# turntable_ir_5.net
KiCad netlist of a schematic drawn in EAGLE
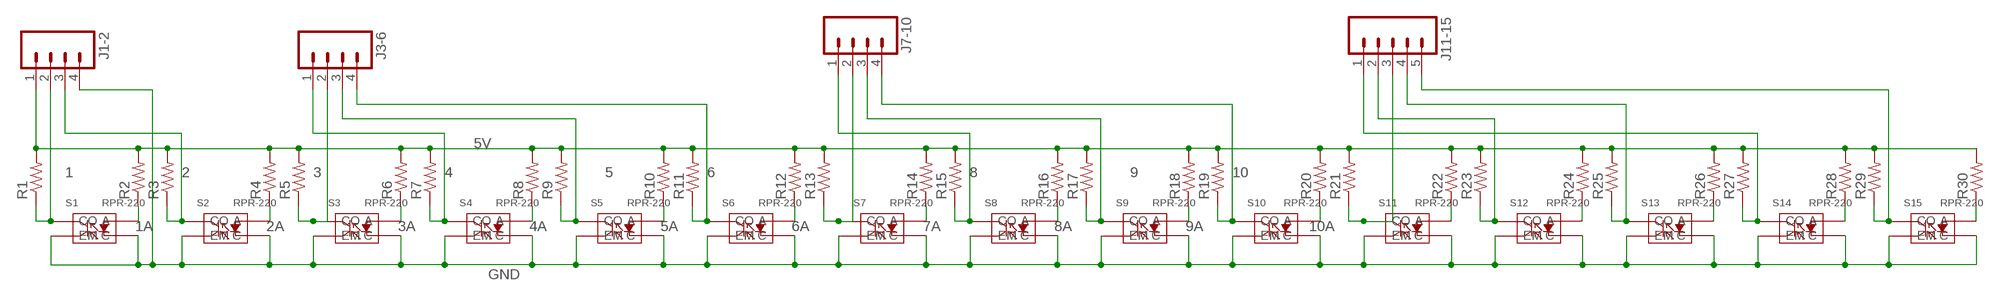
[diagram p0: schematic, sheet 1]

(export (version "E")
  (design (tool "Eeschema 10.0.6"))
  (components
    (comp (ref "J1-2")
      (value "M04NO_SILK_ALL_ROUND")
      (footprint "eagle-import:1X04_NO_SILK_ALL_ROUND")
      (libsource (lib "eagle-import") (part "M04NO_SILK_ALL_ROUND"))
    )
    (comp (ref "J3-6")
      (value "M04NO_SILK_ALL_ROUND")
      (footprint "eagle-import:1X04_NO_SILK_ALL_ROUND")
      (libsource (lib "eagle-import") (part "M04NO_SILK_ALL_ROUND"))
    )
    (comp (ref "J7-10")
      (value "M04NO_SILK_ALL_ROUND")
      (footprint "eagle-import:1X04_NO_SILK_ALL_ROUND")
      (libsource (lib "eagle-import") (part "M04NO_SILK_ALL_ROUND"))
    )
    (comp (ref "J11-15")
      (value "M05NO_SILK")
      (footprint "eagle-import:1X05_NO_SILK")
      (libsource (lib "eagle-import") (part "M05NO_SILK"))
    )
    (comp (ref "R1")
      (value "RESISTOR1206")
      (footprint "eagle-import:1206")
      (libsource (lib "eagle-import") (part "RESISTOR1206"))
    )
    (comp (ref "R2")
      (value "RESISTOR1206")
      (footprint "eagle-import:1206")
      (libsource (lib "eagle-import") (part "RESISTOR1206"))
    )
    (comp (ref "R3")
      (value "RESISTOR1206")
      (footprint "eagle-import:1206")
      (libsource (lib "eagle-import") (part "RESISTOR1206"))
    )
    (comp (ref "R4")
      (value "RESISTOR1206")
      (footprint "eagle-import:1206")
      (libsource (lib "eagle-import") (part "RESISTOR1206"))
    )
    (comp (ref "R5")
      (value "RESISTOR1206")
      (footprint "eagle-import:1206")
      (libsource (lib "eagle-import") (part "RESISTOR1206"))
    )
    (comp (ref "R6")
      (value "RESISTOR1206")
      (footprint "eagle-import:1206")
      (libsource (lib "eagle-import") (part "RESISTOR1206"))
    )
    (comp (ref "R7")
      (value "RESISTOR1206")
      (footprint "eagle-import:1206")
      (libsource (lib "eagle-import") (part "RESISTOR1206"))
    )
    (comp (ref "R8")
      (value "RESISTOR1206")
      (footprint "eagle-import:1206")
      (libsource (lib "eagle-import") (part "RESISTOR1206"))
    )
    (comp (ref "R9")
      (value "RESISTOR1206")
      (footprint "eagle-import:1206")
      (libsource (lib "eagle-import") (part "RESISTOR1206"))
    )
    (comp (ref "R10")
      (value "RESISTOR1206")
      (footprint "eagle-import:1206")
      (libsource (lib "eagle-import") (part "RESISTOR1206"))
    )
    (comp (ref "R11")
      (value "RESISTOR1206")
      (footprint "eagle-import:1206")
      (libsource (lib "eagle-import") (part "RESISTOR1206"))
    )
    (comp (ref "R12")
      (value "RESISTOR1206")
      (footprint "eagle-import:1206")
      (libsource (lib "eagle-import") (part "RESISTOR1206"))
    )
    (comp (ref "R13")
      (value "RESISTOR1206")
      (footprint "eagle-import:1206")
      (libsource (lib "eagle-import") (part "RESISTOR1206"))
    )
    (comp (ref "R14")
      (value "RESISTOR1206")
      (footprint "eagle-import:1206")
      (libsource (lib "eagle-import") (part "RESISTOR1206"))
    )
    (comp (ref "R15")
      (value "RESISTOR1206")
      (footprint "eagle-import:1206")
      (libsource (lib "eagle-import") (part "RESISTOR1206"))
    )
    (comp (ref "R16")
      (value "RESISTOR1206")
      (footprint "eagle-import:1206")
      (libsource (lib "eagle-import") (part "RESISTOR1206"))
    )
    (comp (ref "R17")
      (value "RESISTOR1206")
      (footprint "eagle-import:1206")
      (libsource (lib "eagle-import") (part "RESISTOR1206"))
    )
    (comp (ref "R18")
      (value "RESISTOR1206")
      (footprint "eagle-import:1206")
      (libsource (lib "eagle-import") (part "RESISTOR1206"))
    )
    (comp (ref "R19")
      (value "RESISTOR1206")
      (footprint "eagle-import:1206")
      (libsource (lib "eagle-import") (part "RESISTOR1206"))
    )
    (comp (ref "R20")
      (value "RESISTOR1206")
      (footprint "eagle-import:1206")
      (libsource (lib "eagle-import") (part "RESISTOR1206"))
    )
    (comp (ref "R21")
      (value "RESISTOR1206")
      (footprint "eagle-import:1206")
      (libsource (lib "eagle-import") (part "RESISTOR1206"))
    )
    (comp (ref "R22")
      (value "RESISTOR1206")
      (footprint "eagle-import:1206")
      (libsource (lib "eagle-import") (part "RESISTOR1206"))
    )
    (comp (ref "R23")
      (value "RESISTOR1206")
      (footprint "eagle-import:1206")
      (libsource (lib "eagle-import") (part "RESISTOR1206"))
    )
    (comp (ref "R24")
      (value "RESISTOR1206")
      (footprint "eagle-import:1206")
      (libsource (lib "eagle-import") (part "RESISTOR1206"))
    )
    (comp (ref "R25")
      (value "RESISTOR1206")
      (footprint "eagle-import:1206")
      (libsource (lib "eagle-import") (part "RESISTOR1206"))
    )
    (comp (ref "R26")
      (value "RESISTOR1206")
      (footprint "eagle-import:1206")
      (libsource (lib "eagle-import") (part "RESISTOR1206"))
    )
    (comp (ref "R27")
      (value "RESISTOR1206")
      (footprint "eagle-import:1206")
      (libsource (lib "eagle-import") (part "RESISTOR1206"))
    )
    (comp (ref "R28")
      (value "RESISTOR1206")
      (footprint "eagle-import:1206")
      (libsource (lib "eagle-import") (part "RESISTOR1206"))
    )
    (comp (ref "R29")
      (value "RESISTOR1206")
      (footprint "eagle-import:1206")
      (libsource (lib "eagle-import") (part "RESISTOR1206"))
    )
    (comp (ref "R30")
      (value "RESISTOR1206")
      (footprint "eagle-import:1206")
      (libsource (lib "eagle-import") (part "RESISTOR1206"))
    )
    (comp (ref "S1")
      (value "RPR-220")
      (footprint "eagle-import:RPR-220-6.4X4.9X6.5")
      (libsource (lib "eagle-import") (part "RPR-220"))
    )
    (comp (ref "S2")
      (value "RPR-220")
      (footprint "eagle-import:RPR-220-6.4X4.9X6.5")
      (libsource (lib "eagle-import") (part "RPR-220"))
    )
    (comp (ref "S3")
      (value "RPR-220")
      (footprint "eagle-import:RPR-220-6.4X4.9X6.5")
      (libsource (lib "eagle-import") (part "RPR-220"))
    )
    (comp (ref "S4")
      (value "RPR-220")
      (footprint "eagle-import:RPR-220-6.4X4.9X6.5")
      (libsource (lib "eagle-import") (part "RPR-220"))
    )
    (comp (ref "S5")
      (value "RPR-220")
      (footprint "eagle-import:RPR-220-6.4X4.9X6.5")
      (libsource (lib "eagle-import") (part "RPR-220"))
    )
    (comp (ref "S6")
      (value "RPR-220")
      (footprint "eagle-import:RPR-220-6.4X4.9X6.5")
      (libsource (lib "eagle-import") (part "RPR-220"))
    )
    (comp (ref "S7")
      (value "RPR-220")
      (footprint "eagle-import:RPR-220-6.4X4.9X6.5")
      (libsource (lib "eagle-import") (part "RPR-220"))
    )
    (comp (ref "S8")
      (value "RPR-220")
      (footprint "eagle-import:RPR-220-6.4X4.9X6.5")
      (libsource (lib "eagle-import") (part "RPR-220"))
    )
    (comp (ref "S9")
      (value "RPR-220")
      (footprint "eagle-import:RPR-220-6.4X4.9X6.5")
      (libsource (lib "eagle-import") (part "RPR-220"))
    )
    (comp (ref "S10")
      (value "RPR-220")
      (footprint "eagle-import:RPR-220-6.4X4.9X6.5")
      (libsource (lib "eagle-import") (part "RPR-220"))
    )
    (comp (ref "S11")
      (value "RPR-220")
      (footprint "eagle-import:RPR-220-6.4X4.9X6.5")
      (libsource (lib "eagle-import") (part "RPR-220"))
    )
    (comp (ref "S12")
      (value "RPR-220")
      (footprint "eagle-import:RPR-220-6.4X4.9X6.5")
      (libsource (lib "eagle-import") (part "RPR-220"))
    )
    (comp (ref "S13")
      (value "RPR-220")
      (footprint "eagle-import:RPR-220-6.4X4.9X6.5")
      (libsource (lib "eagle-import") (part "RPR-220"))
    )
    (comp (ref "S14")
      (value "RPR-220")
      (footprint "eagle-import:RPR-220-6.4X4.9X6.5")
      (libsource (lib "eagle-import") (part "RPR-220"))
    )
    (comp (ref "S15")
      (value "RPR-220")
      (footprint "eagle-import:RPR-220-6.4X4.9X6.5")
      (libsource (lib "eagle-import") (part "RPR-220"))
    )
  )
  (nets
    (net (code "1") (name "/1") (class "Default")
      (node (ref "J1-2") (pin "2") (pinfunction "2_2") (pintype "passive"))
      (node (ref "R1") (pin "1") (pinfunction "1_1") (pintype "passive"))
      (node (ref "S1") (pin "P$4") (pinfunction "CO_P$4") (pintype "bidirectional"))
    )
    (net (code "2") (name "/1A") (class "Default")
      (node (ref "R2") (pin "1") (pinfunction "1_1") (pintype "passive"))
      (node (ref "S1") (pin "P$1") (pinfunction "A_P$1") (pintype "bidirectional"))
    )
    (net (code "3") (name "/2") (class "Default")
      (node (ref "J1-2") (pin "3") (pinfunction "3_3") (pintype "passive"))
      (node (ref "R3") (pin "1") (pinfunction "1_1") (pintype "passive"))
      (node (ref "S2") (pin "P$4") (pinfunction "CO_P$4") (pintype "bidirectional"))
    )
    (net (code "4") (name "/2A") (class "Default")
      (node (ref "R4") (pin "1") (pinfunction "1_1") (pintype "passive"))
      (node (ref "S2") (pin "P$1") (pinfunction "A_P$1") (pintype "bidirectional"))
    )
    (net (code "5") (name "/3") (class "Default")
      (node (ref "J3-6") (pin "2") (pinfunction "2_2") (pintype "passive"))
      (node (ref "R5") (pin "1") (pinfunction "1_1") (pintype "passive"))
      (node (ref "S3") (pin "P$4") (pinfunction "CO_P$4") (pintype "bidirectional"))
    )
    (net (code "6") (name "/3A") (class "Default")
      (node (ref "R6") (pin "1") (pinfunction "1_1") (pintype "passive"))
      (node (ref "S3") (pin "P$1") (pinfunction "A_P$1") (pintype "bidirectional"))
    )
    (net (code "7") (name "/4") (class "Default")
      (node (ref "J3-6") (pin "1") (pinfunction "1_1") (pintype "passive"))
      (node (ref "R7") (pin "1") (pinfunction "1_1") (pintype "passive"))
      (node (ref "S4") (pin "P$4") (pinfunction "CO_P$4") (pintype "bidirectional"))
    )
    (net (code "8") (name "/4A") (class "Default")
      (node (ref "R8") (pin "1") (pinfunction "1_1") (pintype "passive"))
      (node (ref "S4") (pin "P$1") (pinfunction "A_P$1") (pintype "bidirectional"))
    )
    (net (code "9") (name "/5") (class "Default")
      (node (ref "J3-6") (pin "3") (pinfunction "3_3") (pintype "passive"))
      (node (ref "R9") (pin "1") (pinfunction "1_1") (pintype "passive"))
      (node (ref "S5") (pin "P$4") (pinfunction "CO_P$4") (pintype "bidirectional"))
    )
    (net (code "10") (name "/5A") (class "Default")
      (node (ref "R10") (pin "1") (pinfunction "1_1") (pintype "passive"))
      (node (ref "S5") (pin "P$1") (pinfunction "A_P$1") (pintype "bidirectional"))
    )
    (net (code "11") (name "/5V") (class "Default")
      (node (ref "J1-2") (pin "1") (pinfunction "1_1") (pintype "passive"))
      (node (ref "R1") (pin "2") (pinfunction "2_2") (pintype "passive"))
      (node (ref "R10") (pin "2") (pinfunction "2_2") (pintype "passive"))
      (node (ref "R11") (pin "2") (pinfunction "2_2") (pintype "passive"))
      (node (ref "R12") (pin "2") (pinfunction "2_2") (pintype "passive"))
      (node (ref "R13") (pin "2") (pinfunction "2_2") (pintype "passive"))
      (node (ref "R14") (pin "2") (pinfunction "2_2") (pintype "passive"))
      (node (ref "R15") (pin "2") (pinfunction "2_2") (pintype "passive"))
      (node (ref "R16") (pin "2") (pinfunction "2_2") (pintype "passive"))
      (node (ref "R17") (pin "2") (pinfunction "2_2") (pintype "passive"))
      (node (ref "R18") (pin "2") (pinfunction "2_2") (pintype "passive"))
      (node (ref "R19") (pin "2") (pinfunction "2_2") (pintype "passive"))
      (node (ref "R2") (pin "2") (pinfunction "2_2") (pintype "passive"))
      (node (ref "R20") (pin "2") (pinfunction "2_2") (pintype "passive"))
      (node (ref "R21") (pin "2") (pinfunction "2_2") (pintype "passive"))
      (node (ref "R22") (pin "2") (pinfunction "2_2") (pintype "passive"))
      (node (ref "R23") (pin "2") (pinfunction "2_2") (pintype "passive"))
      (node (ref "R24") (pin "2") (pinfunction "2_2") (pintype "passive"))
      (node (ref "R25") (pin "2") (pinfunction "2_2") (pintype "passive"))
      (node (ref "R26") (pin "2") (pinfunction "2_2") (pintype "passive"))
      (node (ref "R27") (pin "2") (pinfunction "2_2") (pintype "passive"))
      (node (ref "R28") (pin "2") (pinfunction "2_2") (pintype "passive"))
      (node (ref "R29") (pin "2") (pinfunction "2_2") (pintype "passive"))
      (node (ref "R3") (pin "2") (pinfunction "2_2") (pintype "passive"))
      (node (ref "R30") (pin "2") (pinfunction "2_2") (pintype "passive"))
      (node (ref "R4") (pin "2") (pinfunction "2_2") (pintype "passive"))
      (node (ref "R5") (pin "2") (pinfunction "2_2") (pintype "passive"))
      (node (ref "R6") (pin "2") (pinfunction "2_2") (pintype "passive"))
      (node (ref "R7") (pin "2") (pinfunction "2_2") (pintype "passive"))
      (node (ref "R8") (pin "2") (pinfunction "2_2") (pintype "passive"))
      (node (ref "R9") (pin "2") (pinfunction "2_2") (pintype "passive"))
    )
    (net (code "12") (name "/6") (class "Default")
      (node (ref "J3-6") (pin "4") (pinfunction "4_4") (pintype "passive"))
      (node (ref "R11") (pin "1") (pinfunction "1_1") (pintype "passive"))
      (node (ref "S6") (pin "P$4") (pinfunction "CO_P$4") (pintype "bidirectional"))
    )
    (net (code "13") (name "/6A") (class "Default")
      (node (ref "R12") (pin "1") (pinfunction "1_1") (pintype "passive"))
      (node (ref "S6") (pin "P$1") (pinfunction "A_P$1") (pintype "bidirectional"))
    )
    (net (code "14") (name "/7A") (class "Default")
      (node (ref "R14") (pin "1") (pinfunction "1_1") (pintype "passive"))
      (node (ref "S7") (pin "P$1") (pinfunction "A_P$1") (pintype "bidirectional"))
    )
    (net (code "15") (name "/8") (class "Default")
      (node (ref "J7-10") (pin "1") (pinfunction "1_1") (pintype "passive"))
      (node (ref "R15") (pin "1") (pinfunction "1_1") (pintype "passive"))
      (node (ref "S8") (pin "P$4") (pinfunction "CO_P$4") (pintype "bidirectional"))
    )
    (net (code "16") (name "/8A") (class "Default")
      (node (ref "R16") (pin "1") (pinfunction "1_1") (pintype "passive"))
      (node (ref "S8") (pin "P$1") (pinfunction "A_P$1") (pintype "bidirectional"))
    )
    (net (code "17") (name "/9") (class "Default")
      (node (ref "J7-10") (pin "3") (pinfunction "3_3") (pintype "passive"))
      (node (ref "R17") (pin "1") (pinfunction "1_1") (pintype "passive"))
      (node (ref "S9") (pin "P$4") (pinfunction "CO_P$4") (pintype "bidirectional"))
    )
    (net (code "18") (name "/9A") (class "Default")
      (node (ref "R18") (pin "1") (pinfunction "1_1") (pintype "passive"))
      (node (ref "S9") (pin "P$1") (pinfunction "A_P$1") (pintype "bidirectional"))
    )
    (net (code "19") (name "/10") (class "Default")
      (node (ref "J7-10") (pin "4") (pinfunction "4_4") (pintype "passive"))
      (node (ref "R19") (pin "1") (pinfunction "1_1") (pintype "passive"))
      (node (ref "S10") (pin "P$4") (pinfunction "CO_P$4") (pintype "bidirectional"))
    )
    (net (code "20") (name "/10A") (class "Default")
      (node (ref "R20") (pin "1") (pinfunction "1_1") (pintype "passive"))
      (node (ref "S10") (pin "P$1") (pinfunction "A_P$1") (pintype "bidirectional"))
    )
    (net (code "21") (name "/GND") (class "Default")
      (node (ref "J1-2") (pin "4") (pinfunction "4_4") (pintype "passive"))
      (node (ref "S1") (pin "P$2") (pinfunction "C_P$2") (pintype "bidirectional"))
      (node (ref "S1") (pin "P$3") (pinfunction "EM_P$3") (pintype "bidirectional"))
      (node (ref "S10") (pin "P$2") (pinfunction "C_P$2") (pintype "bidirectional"))
      (node (ref "S10") (pin "P$3") (pinfunction "EM_P$3") (pintype "bidirectional"))
      (node (ref "S11") (pin "P$2") (pinfunction "C_P$2") (pintype "bidirectional"))
      (node (ref "S11") (pin "P$3") (pinfunction "EM_P$3") (pintype "bidirectional"))
      (node (ref "S12") (pin "P$2") (pinfunction "C_P$2") (pintype "bidirectional"))
      (node (ref "S12") (pin "P$3") (pinfunction "EM_P$3") (pintype "bidirectional"))
      (node (ref "S13") (pin "P$2") (pinfunction "C_P$2") (pintype "bidirectional"))
      (node (ref "S13") (pin "P$3") (pinfunction "EM_P$3") (pintype "bidirectional"))
      (node (ref "S14") (pin "P$2") (pinfunction "C_P$2") (pintype "bidirectional"))
      (node (ref "S14") (pin "P$3") (pinfunction "EM_P$3") (pintype "bidirectional"))
      (node (ref "S15") (pin "P$2") (pinfunction "C_P$2") (pintype "bidirectional"))
      (node (ref "S15") (pin "P$3") (pinfunction "EM_P$3") (pintype "bidirectional"))
      (node (ref "S2") (pin "P$2") (pinfunction "C_P$2") (pintype "bidirectional"))
      (node (ref "S2") (pin "P$3") (pinfunction "EM_P$3") (pintype "bidirectional"))
      (node (ref "S3") (pin "P$2") (pinfunction "C_P$2") (pintype "bidirectional"))
      (node (ref "S3") (pin "P$3") (pinfunction "EM_P$3") (pintype "bidirectional"))
      (node (ref "S4") (pin "P$2") (pinfunction "C_P$2") (pintype "bidirectional"))
      (node (ref "S4") (pin "P$3") (pinfunction "EM_P$3") (pintype "bidirectional"))
      (node (ref "S5") (pin "P$2") (pinfunction "C_P$2") (pintype "bidirectional"))
      (node (ref "S5") (pin "P$3") (pinfunction "EM_P$3") (pintype "bidirectional"))
      (node (ref "S6") (pin "P$2") (pinfunction "C_P$2") (pintype "bidirectional"))
      (node (ref "S6") (pin "P$3") (pinfunction "EM_P$3") (pintype "bidirectional"))
      (node (ref "S7") (pin "P$2") (pinfunction "C_P$2") (pintype "bidirectional"))
      (node (ref "S7") (pin "P$3") (pinfunction "EM_P$3") (pintype "bidirectional"))
      (node (ref "S8") (pin "P$2") (pinfunction "C_P$2") (pintype "bidirectional"))
      (node (ref "S8") (pin "P$3") (pinfunction "EM_P$3") (pintype "bidirectional"))
      (node (ref "S9") (pin "P$2") (pinfunction "C_P$2") (pintype "bidirectional"))
      (node (ref "S9") (pin "P$3") (pinfunction "EM_P$3") (pintype "bidirectional"))
    )
    (net (code "22") (name "Net-(S7-CO)") (class "Default")
      (node (ref "J7-10") (pin "2") (pinfunction "2_2") (pintype "passive"))
      (node (ref "R13") (pin "1") (pinfunction "1_1") (pintype "passive"))
      (node (ref "S7") (pin "P$4") (pinfunction "CO_P$4") (pintype "bidirectional"))
    )
    (net (code "23") (name "Net-(S11-A)") (class "Default")
      (node (ref "R22") (pin "1") (pinfunction "1_1") (pintype "passive"))
      (node (ref "S11") (pin "P$1") (pinfunction "A_P$1") (pintype "bidirectional"))
    )
    (net (code "24") (name "Net-(S11-CO)") (class "Default")
      (node (ref "J11-15") (pin "3") (pinfunction "3_3") (pintype "passive"))
      (node (ref "R21") (pin "1") (pinfunction "1_1") (pintype "passive"))
      (node (ref "S11") (pin "P$4") (pinfunction "CO_P$4") (pintype "bidirectional"))
    )
    (net (code "25") (name "Net-(S12-A)") (class "Default")
      (node (ref "R24") (pin "1") (pinfunction "1_1") (pintype "passive"))
      (node (ref "S12") (pin "P$1") (pinfunction "A_P$1") (pintype "bidirectional"))
    )
    (net (code "26") (name "Net-(S12-CO)") (class "Default")
      (node (ref "J11-15") (pin "2") (pinfunction "2_2") (pintype "passive"))
      (node (ref "R23") (pin "1") (pinfunction "1_1") (pintype "passive"))
      (node (ref "S12") (pin "P$4") (pinfunction "CO_P$4") (pintype "bidirectional"))
    )
    (net (code "27") (name "Net-(S13-A)") (class "Default")
      (node (ref "R26") (pin "1") (pinfunction "1_1") (pintype "passive"))
      (node (ref "S13") (pin "P$1") (pinfunction "A_P$1") (pintype "bidirectional"))
    )
    (net (code "28") (name "Net-(S13-CO)") (class "Default")
      (node (ref "J11-15") (pin "4") (pinfunction "4_4") (pintype "passive"))
      (node (ref "R25") (pin "1") (pinfunction "1_1") (pintype "passive"))
      (node (ref "S13") (pin "P$4") (pinfunction "CO_P$4") (pintype "bidirectional"))
    )
    (net (code "29") (name "Net-(S14-A)") (class "Default")
      (node (ref "R28") (pin "1") (pinfunction "1_1") (pintype "passive"))
      (node (ref "S14") (pin "P$1") (pinfunction "A_P$1") (pintype "bidirectional"))
    )
    (net (code "30") (name "Net-(S14-CO)") (class "Default")
      (node (ref "J11-15") (pin "1") (pinfunction "1_1") (pintype "passive"))
      (node (ref "R27") (pin "1") (pinfunction "1_1") (pintype "passive"))
      (node (ref "S14") (pin "P$4") (pinfunction "CO_P$4") (pintype "bidirectional"))
    )
    (net (code "31") (name "Net-(S15-A)") (class "Default")
      (node (ref "R30") (pin "1") (pinfunction "1_1") (pintype "passive"))
      (node (ref "S15") (pin "P$1") (pinfunction "A_P$1") (pintype "bidirectional"))
    )
    (net (code "32") (name "Net-(S15-CO)") (class "Default")
      (node (ref "J11-15") (pin "5") (pinfunction "5_5") (pintype "passive"))
      (node (ref "R29") (pin "1") (pinfunction "1_1") (pintype "passive"))
      (node (ref "S15") (pin "P$4") (pinfunction "CO_P$4") (pintype "bidirectional"))
    )
  )
)
